# tif.net
KiCad netlist of a schematic drawn in EAGLE
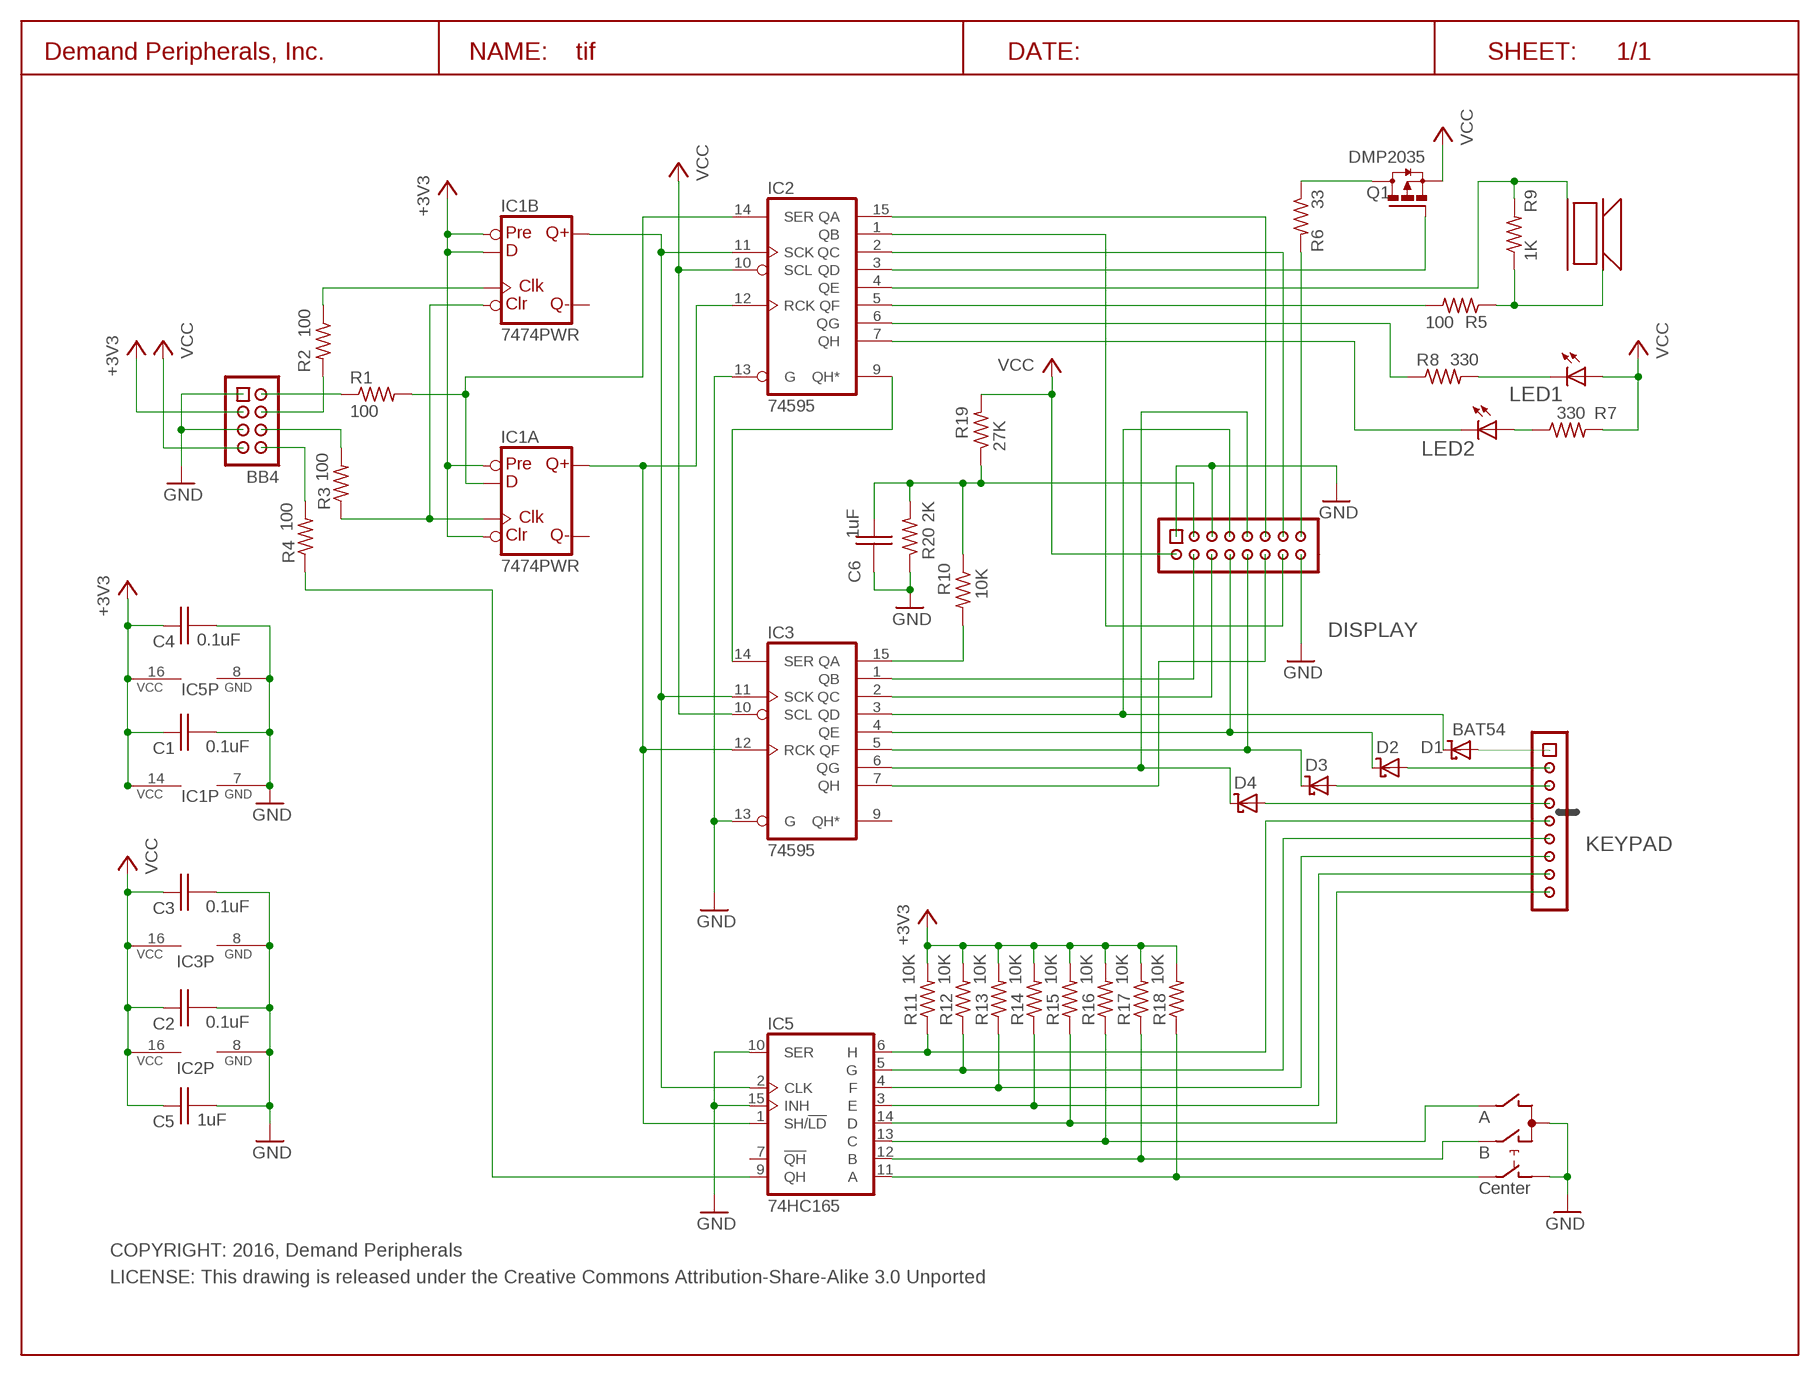
[diagram p0: schematic, sheet 1]

(export (version "E")
  (design (tool "Eeschema 10.0.6"))
  (components
    (comp (ref "2")
      (value "ROTARY_ENCODER_W_SWITCHCTS_V_290")
      (footprint "eagle-import:CTS_290_VERT")
      (libsource (lib "eagle-import") (part "ROTARY_ENCODER_W_SWITCHCTS_V_290"))
    )
    (comp (ref "BB4")
      (value "Hdr_4x2")
      (footprint "eagle-import:HDR-4X2")
      (libsource (lib "eagle-import") (part "HDR-4X2-SHR"))
    )
    (comp (ref "C1")
      (value "0.1uF")
      (footprint "eagle-import:C0603")
      (libsource (lib "eagle-import") (part "C0.1UF_C0603"))
    )
    (comp (ref "C2")
      (value "0.1uF")
      (footprint "eagle-import:C0603")
      (libsource (lib "eagle-import") (part "C0.1UF_C0603"))
    )
    (comp (ref "C3")
      (value "0.1uF")
      (footprint "eagle-import:C0603")
      (libsource (lib "eagle-import") (part "C0.1UF_C0603"))
    )
    (comp (ref "C4")
      (value "0.1uF")
      (footprint "eagle-import:C0603")
      (libsource (lib "eagle-import") (part "C0.1UF_C0603"))
    )
    (comp (ref "C5")
      (value "1uF")
      (footprint "eagle-import:C0603")
      (libsource (lib "eagle-import") (part "C0.1UF_C0603"))
    )
    (comp (ref "C6")
      (value "1uF")
      (footprint "eagle-import:C0603")
      (libsource (lib "eagle-import") (part "C1.0UF_C0603"))
    )
    (comp (ref "D1")
      (value "BAT54")
      (footprint "eagle-import:SOT23")
      (libsource (lib "eagle-import") (part "BAT54"))
    )
    (comp (ref "D2")
      (value "BAT54")
      (footprint "eagle-import:SOT23")
      (libsource (lib "eagle-import") (part "BAT54"))
    )
    (comp (ref "D3")
      (value "BAT54")
      (footprint "eagle-import:SOT23")
      (libsource (lib "eagle-import") (part "BAT54"))
    )
    (comp (ref "D4")
      (value "BAT54")
      (footprint "eagle-import:SOT23")
      (libsource (lib "eagle-import") (part "BAT54"))
    )
    (comp (ref "DISPLAY")
      (value "HDR-8X2")
      (footprint "eagle-import:HDR-8X2")
      (libsource (lib "eagle-import") (part "HDR-8X2"))
    )
    (comp (ref "IC1")
      (value "7474PWR")
      (footprint "eagle-import:SO14")
      (libsource (lib "eagle-import") (part "74AHC74SS"))
    )
    (comp (ref "IC2")
      (value "74595")
      (footprint "eagle-import:SO16")
      (libsource (lib "eagle-import") (part "74595"))
    )
    (comp (ref "IC3")
      (value "74595")
      (footprint "eagle-import:SO16")
      (libsource (lib "eagle-import") (part "74595"))
    )
    (comp (ref "IC5")
      (value "74HC165")
      (footprint "eagle-import:SO16")
      (libsource (lib "eagle-import") (part "74HC165"))
    )
    (comp (ref "KEYPAD")
      (value "HDR-9X1")
      (footprint "eagle-import:HDR-9X1")
      (libsource (lib "eagle-import") (part "HDR-9X1"))
    )
    (comp (ref "LED1")
      (value "LED-0805-GRN")
      (footprint "eagle-import:0805")
      (libsource (lib "eagle-import") (part "LED-0805-GRN"))
    )
    (comp (ref "LED2")
      (value "LED-0805-RED")
      (footprint "eagle-import:0805")
      (libsource (lib "eagle-import") (part "LED-0805-RED"))
    )
    (comp (ref "Q1")
      (value "DMP2035")
      (footprint "eagle-import:SOT23")
      (libsource (lib "eagle-import") (part "DMP2035"))
    )
    (comp (ref "R1")
      (value "100")
      (footprint "eagle-import:R0603")
      (libsource (lib "eagle-import") (part "R100_R0603"))
    )
    (comp (ref "R2")
      (value "100")
      (footprint "eagle-import:R0603")
      (libsource (lib "eagle-import") (part "R100_R0603"))
    )
    (comp (ref "R3")
      (value "100")
      (footprint "eagle-import:R0603")
      (libsource (lib "eagle-import") (part "R100_R0603"))
    )
    (comp (ref "R4")
      (value "100")
      (footprint "eagle-import:R0603")
      (libsource (lib "eagle-import") (part "R100_R0603"))
    )
    (comp (ref "R5")
      (value "100")
      (footprint "eagle-import:R0603")
      (libsource (lib "eagle-import") (part "R100_R0603"))
    )
    (comp (ref "R6")
      (value "33")
      (footprint "eagle-import:R0603")
      (libsource (lib "eagle-import") (part "R33R0603"))
    )
    (comp (ref "R7")
      (value "330")
      (footprint "eagle-import:R0603")
      (libsource (lib "eagle-import") (part "R330_R0603"))
    )
    (comp (ref "R8")
      (value "330")
      (footprint "eagle-import:R0603")
      (libsource (lib "eagle-import") (part "R330_R0603"))
    )
    (comp (ref "R9")
      (value "1K")
      (footprint "eagle-import:R0603")
      (libsource (lib "eagle-import") (part "R1K_R0603"))
    )
    (comp (ref "R10")
      (value "10K")
      (footprint "eagle-import:R0603")
      (libsource (lib "eagle-import") (part "R10K_R0603"))
    )
    (comp (ref "R11")
      (value "10K")
      (footprint "eagle-import:R0603")
      (libsource (lib "eagle-import") (part "R10K_R0603"))
    )
    (comp (ref "R12")
      (value "10K")
      (footprint "eagle-import:R0603")
      (libsource (lib "eagle-import") (part "R10K_R0603"))
    )
    (comp (ref "R13")
      (value "10K")
      (footprint "eagle-import:R0603")
      (libsource (lib "eagle-import") (part "R10K_R0603"))
    )
    (comp (ref "R14")
      (value "10K")
      (footprint "eagle-import:R0603")
      (libsource (lib "eagle-import") (part "R10K_R0603"))
    )
    (comp (ref "R15")
      (value "10K")
      (footprint "eagle-import:R0603")
      (libsource (lib "eagle-import") (part "R10K_R0603"))
    )
    (comp (ref "R16")
      (value "10K")
      (footprint "eagle-import:R0603")
      (libsource (lib "eagle-import") (part "R10K_R0603"))
    )
    (comp (ref "R17")
      (value "10K")
      (footprint "eagle-import:R0603")
      (libsource (lib "eagle-import") (part "R10K_R0603"))
    )
    (comp (ref "R18")
      (value "10K")
      (footprint "eagle-import:R0603")
      (libsource (lib "eagle-import") (part "R10K_R0603"))
    )
    (comp (ref "R19")
      (value "27K")
      (footprint "eagle-import:R0603")
      (libsource (lib "eagle-import") (part "R27K_R0603"))
    )
    (comp (ref "R20")
      (value "2K")
      (footprint "eagle-import:R0603")
      (libsource (lib "eagle-import") (part "R2K_R0603"))
    )
    (comp (ref "SPK1")
      (value "PKM13EPY")
      (footprint "eagle-import:PKM13EPY")
      (libsource (lib "eagle-import") (part "PKM13EPY"))
    )
    (comp (ref "U$5")
      (value "DP_FRAME_L")
      (footprint "eagle-import:LETTER_L")
      (libsource (lib "eagle-import") (part "DP_FRAME_L"))
    )
  )
  (nets
    (net (code "1") (name "+3V3") (class "Default")
      (node (ref "BB4") (pin "3") (pinfunction "3_3") (pintype "passive"))
      (node (ref "C1") (pin "1") (pinfunction "1_1") (pintype "passive"))
      (node (ref "C4") (pin "1") (pinfunction "1_1") (pintype "passive"))
      (node (ref "IC1") (pin "1") (pinfunction "CLR_1") (pintype "input"))
      (node (ref "IC1") (pin "10") (pinfunction "PRE_10") (pintype "input"))
      (node (ref "IC1") (pin "12") (pinfunction "D_12") (pintype "input"))
      (node (ref "IC1") (pin "14") (pinfunction "VCC_14") (pintype "power_in"))
      (node (ref "IC1") (pin "4") (pinfunction "PRE_4") (pintype "input"))
      (node (ref "IC5") (pin "16") (pinfunction "VCC_16") (pintype "power_in"))
      (node (ref "R11") (pin "2") (pinfunction "2_2") (pintype "passive"))
      (node (ref "R12") (pin "2") (pinfunction "2_2") (pintype "passive"))
      (node (ref "R13") (pin "2") (pinfunction "2_2") (pintype "passive"))
      (node (ref "R14") (pin "2") (pinfunction "2_2") (pintype "passive"))
      (node (ref "R15") (pin "2") (pinfunction "2_2") (pintype "passive"))
      (node (ref "R16") (pin "2") (pinfunction "2_2") (pintype "passive"))
      (node (ref "R17") (pin "2") (pinfunction "2_2") (pintype "passive"))
      (node (ref "R18") (pin "2") (pinfunction "2_2") (pintype "passive"))
    )
    (net (code "2") (name "GND") (class "Default")
      (node (ref "2") (pin "C") (pinfunction "C_C") (pintype "passive"))
      (node (ref "2") (pin "D") (pinfunction "D_D") (pintype "passive"))
      (node (ref "BB4") (pin "1") (pinfunction "1_1") (pintype "passive"))
      (node (ref "BB4") (pin "5") (pinfunction "5_5") (pintype "passive"))
      (node (ref "C1") (pin "2") (pinfunction "2_2") (pintype "passive"))
      (node (ref "C2") (pin "2") (pinfunction "2_2") (pintype "passive"))
      (node (ref "C3") (pin "2") (pinfunction "2_2") (pintype "passive"))
      (node (ref "C4") (pin "2") (pinfunction "2_2") (pintype "passive"))
      (node (ref "C5") (pin "2") (pinfunction "2_2") (pintype "passive"))
      (node (ref "C6") (pin "2") (pinfunction "2_2") (pintype "passive"))
      (node (ref "DISPLAY") (pin "1") (pinfunction "1_1") (pintype "passive"))
      (node (ref "DISPLAY") (pin "16") (pinfunction "16_16") (pintype "passive"))
      (node (ref "DISPLAY") (pin "5") (pinfunction "5_5") (pintype "passive"))
      (node (ref "IC1") (pin "7") (pinfunction "GND_7") (pintype "power_in"))
      (node (ref "IC2") (pin "13") (pinfunction "G_13") (pintype "input"))
      (node (ref "IC2") (pin "8") (pinfunction "GND_8") (pintype "power_in"))
      (node (ref "IC3") (pin "13") (pinfunction "G_13") (pintype "input"))
      (node (ref "IC3") (pin "8") (pinfunction "GND_8") (pintype "power_in"))
      (node (ref "IC5") (pin "10") (pinfunction "SER_10") (pintype "input"))
      (node (ref "IC5") (pin "15") (pinfunction "INH_15") (pintype "input"))
      (node (ref "IC5") (pin "8") (pinfunction "GND_8") (pintype "power_in"))
      (node (ref "R20") (pin "1") (pinfunction "1_1") (pintype "passive"))
    )
    (net (code "3") (name "Net-(BB4-Pad2)") (class "Default")
      (node (ref "BB4") (pin "2") (pinfunction "2_2") (pintype "passive"))
      (node (ref "R1") (pin "1") (pinfunction "1_1") (pintype "passive"))
    )
    (net (code "4") (name "Net-(BB4-Pad4)") (class "Default")
      (node (ref "BB4") (pin "4") (pinfunction "4_4") (pintype "passive"))
      (node (ref "R2") (pin "2") (pinfunction "2_2") (pintype "passive"))
    )
    (net (code "5") (name "Net-(BB4-Pad6)") (class "Default")
      (node (ref "BB4") (pin "6") (pinfunction "6_6") (pintype "passive"))
      (node (ref "R3") (pin "2") (pinfunction "2_2") (pintype "passive"))
    )
    (net (code "6") (name "Net-(BB4-Pad8)") (class "Default")
      (node (ref "BB4") (pin "8") (pinfunction "8_8") (pintype "passive"))
      (node (ref "R4") (pin "2") (pinfunction "2_2") (pintype "passive"))
    )
    (net (code "7") (name "Net-(C6-Pad1)") (class "Default")
      (node (ref "C6") (pin "1") (pinfunction "1_1") (pintype "passive"))
      (node (ref "DISPLAY") (pin "3") (pinfunction "3_3") (pintype "passive"))
      (node (ref "R10") (pin "1") (pinfunction "1_1") (pintype "passive"))
      (node (ref "R19") (pin "1") (pinfunction "1_1") (pintype "passive"))
      (node (ref "R20") (pin "2") (pinfunction "2_2") (pintype "passive"))
    )
    (net (code "8") (name "Net-(D1-A)") (class "Default")
      (node (ref "D1") (pin "1") (pinfunction "A_1") (pintype "passive"))
      (node (ref "KEYPAD") (pin "1") (pinfunction "1_1") (pintype "passive"))
    )
    (net (code "9") (name "Net-(D1-CC)") (class "Default")
      (node (ref "D1") (pin "3") (pinfunction "CC_3") (pintype "passive"))
      (node (ref "DISPLAY") (pin "7") (pinfunction "7_7") (pintype "passive"))
      (node (ref "IC3") (pin "3") (pinfunction "QD_3") (pintype "tri_state"))
    )
    (net (code "10") (name "Net-(D2-A)") (class "Default")
      (node (ref "D2") (pin "1") (pinfunction "A_1") (pintype "passive"))
      (node (ref "KEYPAD") (pin "2") (pinfunction "2_2") (pintype "passive"))
    )
    (net (code "11") (name "Net-(D2-CC)") (class "Default")
      (node (ref "D2") (pin "3") (pinfunction "CC_3") (pintype "passive"))
      (node (ref "DISPLAY") (pin "8") (pinfunction "8_8") (pintype "passive"))
      (node (ref "IC3") (pin "4") (pinfunction "QE_4") (pintype "tri_state"))
    )
    (net (code "12") (name "Net-(D3-A)") (class "Default")
      (node (ref "D3") (pin "1") (pinfunction "A_1") (pintype "passive"))
      (node (ref "KEYPAD") (pin "3") (pinfunction "3_3") (pintype "passive"))
    )
    (net (code "13") (name "Net-(D3-CC)") (class "Default")
      (node (ref "D3") (pin "3") (pinfunction "CC_3") (pintype "passive"))
      (node (ref "DISPLAY") (pin "10") (pinfunction "10_10") (pintype "passive"))
      (node (ref "IC3") (pin "5") (pinfunction "QF_5") (pintype "tri_state"))
    )
    (net (code "14") (name "Net-(D4-A)") (class "Default")
      (node (ref "D4") (pin "1") (pinfunction "A_1") (pintype "passive"))
      (node (ref "KEYPAD") (pin "4") (pinfunction "4_4") (pintype "passive"))
    )
    (net (code "15") (name "Net-(D4-CC)") (class "Default")
      (node (ref "D4") (pin "3") (pinfunction "CC_3") (pintype "passive"))
      (node (ref "DISPLAY") (pin "9") (pinfunction "9_9") (pintype "passive"))
      (node (ref "IC3") (pin "6") (pinfunction "QG_6") (pintype "tri_state"))
    )
    (net (code "16") (name "Net-(DISPLAY-Pad15)") (class "Default")
      (node (ref "DISPLAY") (pin "15") (pinfunction "15_15") (pintype "passive"))
      (node (ref "R6") (pin "2") (pinfunction "2_2") (pintype "passive"))
    )
    (net (code "17") (name "Net-(IC1A-CLK)") (class "Default")
      (node (ref "IC1") (pin "13") (pinfunction "CLR_13") (pintype "input"))
      (node (ref "IC1") (pin "3") (pinfunction "CLK_3") (pintype "input"))
      (node (ref "R3") (pin "1") (pinfunction "1_1") (pintype "passive"))
    )
    (net (code "18") (name "Net-(IC1A-D)") (class "Default")
      (node (ref "IC1") (pin "2") (pinfunction "D_2") (pintype "input"))
      (node (ref "IC2") (pin "14") (pinfunction "SER_14") (pintype "input"))
      (node (ref "R1") (pin "2") (pinfunction "2_2") (pintype "passive"))
    )
    (net (code "19") (name "Net-(IC1A-Q)") (class "Default")
      (node (ref "IC1") (pin "5") (pinfunction "Q_5") (pintype "output"))
      (node (ref "IC2") (pin "12") (pinfunction "RCK_12") (pintype "input"))
      (node (ref "IC3") (pin "12") (pinfunction "RCK_12") (pintype "input"))
      (node (ref "IC5") (pin "1") (pinfunction "SH/~{LD}_1") (pintype "input"))
    )
    (net (code "20") (name "Net-(IC1B-CLK)") (class "Default")
      (node (ref "IC1") (pin "11") (pinfunction "CLK_11") (pintype "input"))
      (node (ref "R2") (pin "1") (pinfunction "1_1") (pintype "passive"))
    )
    (net (code "21") (name "Net-(IC1B-Q)") (class "Default")
      (node (ref "IC1") (pin "9") (pinfunction "Q_9") (pintype "output"))
      (node (ref "IC2") (pin "11") (pinfunction "SCK_11") (pintype "input"))
      (node (ref "IC3") (pin "11") (pinfunction "SCK_11") (pintype "input"))
      (node (ref "IC5") (pin "2") (pinfunction "CLK_2") (pintype "input"))
    )
    (net (code "22") (name "Net-(IC2A-QA)") (class "Default")
      (node (ref "DISPLAY") (pin "11") (pinfunction "11_11") (pintype "passive"))
      (node (ref "IC2") (pin "15") (pinfunction "QA_15") (pintype "tri_state"))
    )
    (net (code "23") (name "Net-(IC2A-QB)") (class "Default")
      (node (ref "DISPLAY") (pin "14") (pinfunction "14_14") (pintype "passive"))
      (node (ref "IC2") (pin "1") (pinfunction "QB_1") (pintype "tri_state"))
    )
    (net (code "24") (name "Net-(IC2A-QC)") (class "Default")
      (node (ref "DISPLAY") (pin "13") (pinfunction "13_13") (pintype "passive"))
      (node (ref "IC2") (pin "2") (pinfunction "QC_2") (pintype "tri_state"))
    )
    (net (code "25") (name "Net-(IC2A-QD)") (class "Default")
      (node (ref "IC2") (pin "3") (pinfunction "QD_3") (pintype "tri_state"))
      (node (ref "Q1") (pin "1") (pinfunction "G_1") (pintype "passive"))
    )
    (net (code "26") (name "Net-(IC2A-QE)") (class "Default")
      (node (ref "IC2") (pin "4") (pinfunction "QE_4") (pintype "tri_state"))
      (node (ref "R9") (pin "2") (pinfunction "2_2") (pintype "passive"))
      (node (ref "SPK1") (pin "1") (pinfunction "GND1_1") (pintype "passive"))
    )
    (net (code "27") (name "Net-(IC2A-QF)") (class "Default")
      (node (ref "IC2") (pin "5") (pinfunction "QF_5") (pintype "tri_state"))
      (node (ref "R5") (pin "2") (pinfunction "2_2") (pintype "passive"))
    )
    (net (code "28") (name "Net-(IC2A-QG)") (class "Default")
      (node (ref "IC2") (pin "6") (pinfunction "QG_6") (pintype "tri_state"))
      (node (ref "R8") (pin "1") (pinfunction "1_1") (pintype "passive"))
    )
    (net (code "29") (name "Net-(IC2A-QH)") (class "Default")
      (node (ref "IC2") (pin "7") (pinfunction "QH_7") (pintype "tri_state"))
      (node (ref "LED2") (pin "C") (pinfunction "C_C") (pintype "passive"))
    )
    (net (code "30") (name "Net-(IC2A-QH*)") (class "Default")
      (node (ref "IC2") (pin "9") (pinfunction "QH*_9") (pintype "tri_state"))
      (node (ref "IC3") (pin "14") (pinfunction "SER_14") (pintype "input"))
    )
    (net (code "31") (name "Net-(IC3A-QA)") (class "Default")
      (node (ref "IC3") (pin "15") (pinfunction "QA_15") (pintype "tri_state"))
      (node (ref "R10") (pin "2") (pinfunction "2_2") (pintype "passive"))
    )
    (net (code "32") (name "Net-(IC3A-QB)") (class "Default")
      (node (ref "DISPLAY") (pin "4") (pinfunction "4_4") (pintype "passive"))
      (node (ref "IC3") (pin "1") (pinfunction "QB_1") (pintype "tri_state"))
    )
    (net (code "33") (name "Net-(IC3A-QC)") (class "Default")
      (node (ref "DISPLAY") (pin "6") (pinfunction "6_6") (pintype "passive"))
      (node (ref "IC3") (pin "2") (pinfunction "QC_2") (pintype "tri_state"))
    )
    (net (code "34") (name "Net-(IC3A-QH)") (class "Default")
      (node (ref "DISPLAY") (pin "12") (pinfunction "12_12") (pintype "passive"))
      (node (ref "IC3") (pin "7") (pinfunction "QH_7") (pintype "tri_state"))
    )
    (net (code "35") (name "Net-(IC5A-A)") (class "Default")
      (node (ref "2") (pin "E") (pinfunction "E_E") (pintype "passive"))
      (node (ref "IC5") (pin "11") (pinfunction "A_11") (pintype "input"))
      (node (ref "R18") (pin "1") (pinfunction "1_1") (pintype "passive"))
    )
    (net (code "36") (name "Net-(IC5A-B)") (class "Default")
      (node (ref "2") (pin "A") (pinfunction "A_A") (pintype "passive"))
      (node (ref "IC5") (pin "12") (pinfunction "B_12") (pintype "input"))
      (node (ref "R17") (pin "1") (pinfunction "1_1") (pintype "passive"))
    )
    (net (code "37") (name "Net-(IC5A-C)") (class "Default")
      (node (ref "2") (pin "B") (pinfunction "B_B") (pintype "passive"))
      (node (ref "IC5") (pin "13") (pinfunction "C_13") (pintype "input"))
      (node (ref "R16") (pin "1") (pinfunction "1_1") (pintype "passive"))
    )
    (net (code "38") (name "Net-(IC5A-D)") (class "Default")
      (node (ref "IC5") (pin "14") (pinfunction "D_14") (pintype "input"))
      (node (ref "KEYPAD") (pin "9") (pinfunction "9_9") (pintype "passive"))
      (node (ref "R15") (pin "1") (pinfunction "1_1") (pintype "passive"))
    )
    (net (code "39") (name "Net-(IC5A-E)") (class "Default")
      (node (ref "IC5") (pin "3") (pinfunction "E_3") (pintype "input"))
      (node (ref "KEYPAD") (pin "8") (pinfunction "8_8") (pintype "passive"))
      (node (ref "R14") (pin "1") (pinfunction "1_1") (pintype "passive"))
    )
    (net (code "40") (name "Net-(IC5A-F)") (class "Default")
      (node (ref "IC5") (pin "4") (pinfunction "F_4") (pintype "input"))
      (node (ref "KEYPAD") (pin "7") (pinfunction "7_7") (pintype "passive"))
      (node (ref "R13") (pin "1") (pinfunction "1_1") (pintype "passive"))
    )
    (net (code "41") (name "Net-(IC5A-G)") (class "Default")
      (node (ref "IC5") (pin "5") (pinfunction "G_5") (pintype "input"))
      (node (ref "KEYPAD") (pin "6") (pinfunction "6_6") (pintype "passive"))
      (node (ref "R12") (pin "1") (pinfunction "1_1") (pintype "passive"))
    )
    (net (code "42") (name "Net-(IC5A-H)") (class "Default")
      (node (ref "IC5") (pin "6") (pinfunction "H_6") (pintype "input"))
      (node (ref "KEYPAD") (pin "5") (pinfunction "5_5") (pintype "passive"))
      (node (ref "R11") (pin "1") (pinfunction "1_1") (pintype "passive"))
    )
    (net (code "43") (name "Net-(IC5A-QH)") (class "Default")
      (node (ref "IC5") (pin "9") (pinfunction "QH_9") (pintype "output"))
      (node (ref "R4") (pin "1") (pinfunction "1_1") (pintype "passive"))
    )
    (net (code "44") (name "Net-(LED1-PadC)") (class "Default")
      (node (ref "LED1") (pin "C") (pinfunction "C_C") (pintype "passive"))
      (node (ref "R8") (pin "2") (pinfunction "2_2") (pintype "passive"))
    )
    (net (code "45") (name "Net-(LED2-PadA)") (class "Default")
      (node (ref "LED2") (pin "A") (pinfunction "A_A") (pintype "passive"))
      (node (ref "R7") (pin "1") (pinfunction "1_1") (pintype "passive"))
    )
    (net (code "46") (name "Net-(Q1-D)") (class "Default")
      (node (ref "Q1") (pin "3") (pinfunction "D_3") (pintype "passive"))
      (node (ref "R6") (pin "1") (pinfunction "1_1") (pintype "passive"))
    )
    (net (code "47") (name "Net-(SPK1-GND2)") (class "Default")
      (node (ref "R5") (pin "1") (pinfunction "1_1") (pintype "passive"))
      (node (ref "R9") (pin "1") (pinfunction "1_1") (pintype "passive"))
      (node (ref "SPK1") (pin "2") (pinfunction "GND2_2") (pintype "passive"))
    )
    (net (code "48") (name "VCC") (class "Default")
      (node (ref "BB4") (pin "7") (pinfunction "7_7") (pintype "passive"))
      (node (ref "C2") (pin "1") (pinfunction "1_1") (pintype "passive"))
      (node (ref "C3") (pin "1") (pinfunction "1_1") (pintype "passive"))
      (node (ref "C5") (pin "1") (pinfunction "1_1") (pintype "passive"))
      (node (ref "DISPLAY") (pin "2") (pinfunction "2_2") (pintype "passive"))
      (node (ref "IC2") (pin "10") (pinfunction "SCL_10") (pintype "input"))
      (node (ref "IC2") (pin "16") (pinfunction "VCC_16") (pintype "power_in"))
      (node (ref "IC3") (pin "10") (pinfunction "SCL_10") (pintype "input"))
      (node (ref "IC3") (pin "16") (pinfunction "VCC_16") (pintype "power_in"))
      (node (ref "LED1") (pin "A") (pinfunction "A_A") (pintype "passive"))
      (node (ref "Q1") (pin "2") (pinfunction "S_2") (pintype "passive"))
      (node (ref "R19") (pin "2") (pinfunction "2_2") (pintype "passive"))
      (node (ref "R7") (pin "2") (pinfunction "2_2") (pintype "passive"))
    )
    (net (code "49") (name "unconnected-(IC1A-~{Q}-Pad6)") (class "Default")
      (node (ref "IC1") (pin "6") (pinfunction "~{Q}_6") (pintype "output"))
    )
    (net (code "50") (name "unconnected-(IC1B-~{Q}-Pad8)") (class "Default")
      (node (ref "IC1") (pin "8") (pinfunction "~{Q}_8") (pintype "output"))
    )
    (net (code "51") (name "unconnected-(IC3A-QH*-Pad9)") (class "Default")
      (node (ref "IC3") (pin "9") (pinfunction "QH*_9") (pintype "tri_state"))
    )
    (net (code "52") (name "unconnected-(IC5A-~{QH}-Pad7)") (class "Default")
      (node (ref "IC5") (pin "7") (pinfunction "~{QH}_7") (pintype "output"))
    )
  )
)
